# MHR15-inverter_current_sensors-v2.net
KiCad netlist of a schematic drawn in EAGLE
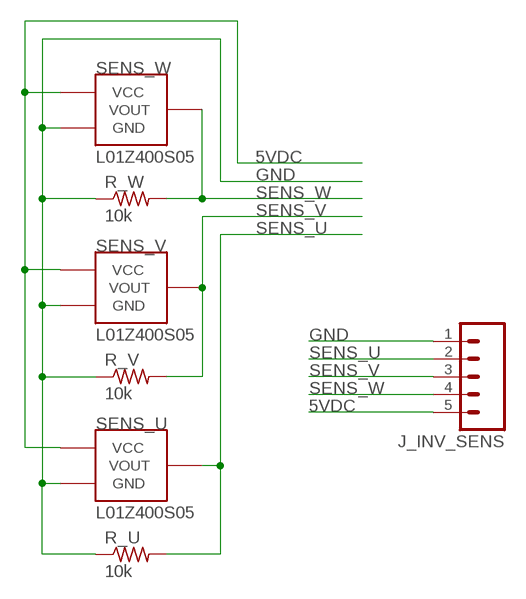
[diagram p0: schematic, sheet 1]

(export (version "E")
  (design (tool "Eeschema 10.0.6"))
  (components
    (comp (ref "J_INV_SENS")
      (value "M05LOCK")
      (footprint "eagle-import:1X05_LOCK")
      (libsource (lib "eagle-import") (part "M05LOCK"))
    )
    (comp (ref "R_U")
      (value "10k")
      (footprint "eagle-import:R0603")
      (libsource (lib "eagle-import") (part "R-US_R0603"))
    )
    (comp (ref "R_V")
      (value "10k")
      (footprint "eagle-import:R0603")
      (libsource (lib "eagle-import") (part "R-US_R0603"))
    )
    (comp (ref "R_W")
      (value "10k")
      (footprint "eagle-import:R0603")
      (libsource (lib "eagle-import") (part "R-US_R0603"))
    )
    (comp (ref "SENS_U")
      (value "L01Z400S05")
      (footprint "eagle-import:L01Z400S05")
      (fields (field (name "MANUFACTURER") "Tamura"))
      (libsource (lib "eagle-import") (part "L01Z400S05"))
    )
    (comp (ref "SENS_V")
      (value "L01Z400S05")
      (footprint "eagle-import:L01Z400S05")
      (fields (field (name "MANUFACTURER") "Tamura"))
      (libsource (lib "eagle-import") (part "L01Z400S05"))
    )
    (comp (ref "SENS_W")
      (value "L01Z400S05")
      (footprint "eagle-import:L01Z400S05")
      (fields (field (name "MANUFACTURER") "Tamura"))
      (libsource (lib "eagle-import") (part "L01Z400S05"))
    )
  )
  (nets
    (net (code "1") (name "/5VDC") (class "Default")
      (node (ref "J_INV_SENS") (pin "5") (pinfunction "5_5") (pintype "passive"))
      (node (ref "SENS_U") (pin "VCC") (pinfunction "VCC_VCC") (pintype "bidirectional"))
      (node (ref "SENS_V") (pin "VCC") (pinfunction "VCC_VCC") (pintype "bidirectional"))
      (node (ref "SENS_W") (pin "VCC") (pinfunction "VCC_VCC") (pintype "bidirectional"))
    )
    (net (code "2") (name "/GND") (class "Default")
      (node (ref "J_INV_SENS") (pin "1") (pinfunction "1_1") (pintype "passive"))
      (node (ref "R_U") (pin "1") (pinfunction "1_1") (pintype "passive"))
      (node (ref "R_V") (pin "1") (pinfunction "1_1") (pintype "passive"))
      (node (ref "R_W") (pin "1") (pinfunction "1_1") (pintype "passive"))
      (node (ref "SENS_U") (pin "GND") (pinfunction "GND_GND") (pintype "bidirectional"))
      (node (ref "SENS_V") (pin "GND") (pinfunction "GND_GND") (pintype "bidirectional"))
      (node (ref "SENS_W") (pin "GND") (pinfunction "GND_GND") (pintype "bidirectional"))
    )
    (net (code "3") (name "/SENS_U") (class "Default")
      (node (ref "J_INV_SENS") (pin "2") (pinfunction "2_2") (pintype "passive"))
      (node (ref "R_U") (pin "2") (pinfunction "2_2") (pintype "passive"))
      (node (ref "SENS_U") (pin "VOUT") (pinfunction "VOUT_VOUT") (pintype "bidirectional"))
    )
    (net (code "4") (name "/SENS_V") (class "Default")
      (node (ref "J_INV_SENS") (pin "3") (pinfunction "3_3") (pintype "passive"))
      (node (ref "R_V") (pin "2") (pinfunction "2_2") (pintype "passive"))
      (node (ref "SENS_V") (pin "VOUT") (pinfunction "VOUT_VOUT") (pintype "bidirectional"))
    )
    (net (code "5") (name "/SENS_W") (class "Default")
      (node (ref "J_INV_SENS") (pin "4") (pinfunction "4_4") (pintype "passive"))
      (node (ref "R_W") (pin "2") (pinfunction "2_2") (pintype "passive"))
      (node (ref "SENS_W") (pin "VOUT") (pinfunction "VOUT_VOUT") (pintype "bidirectional"))
    )
  )
)
